# GrooveGrid.net
KiCad netlist of a schematic drawn in EAGLE
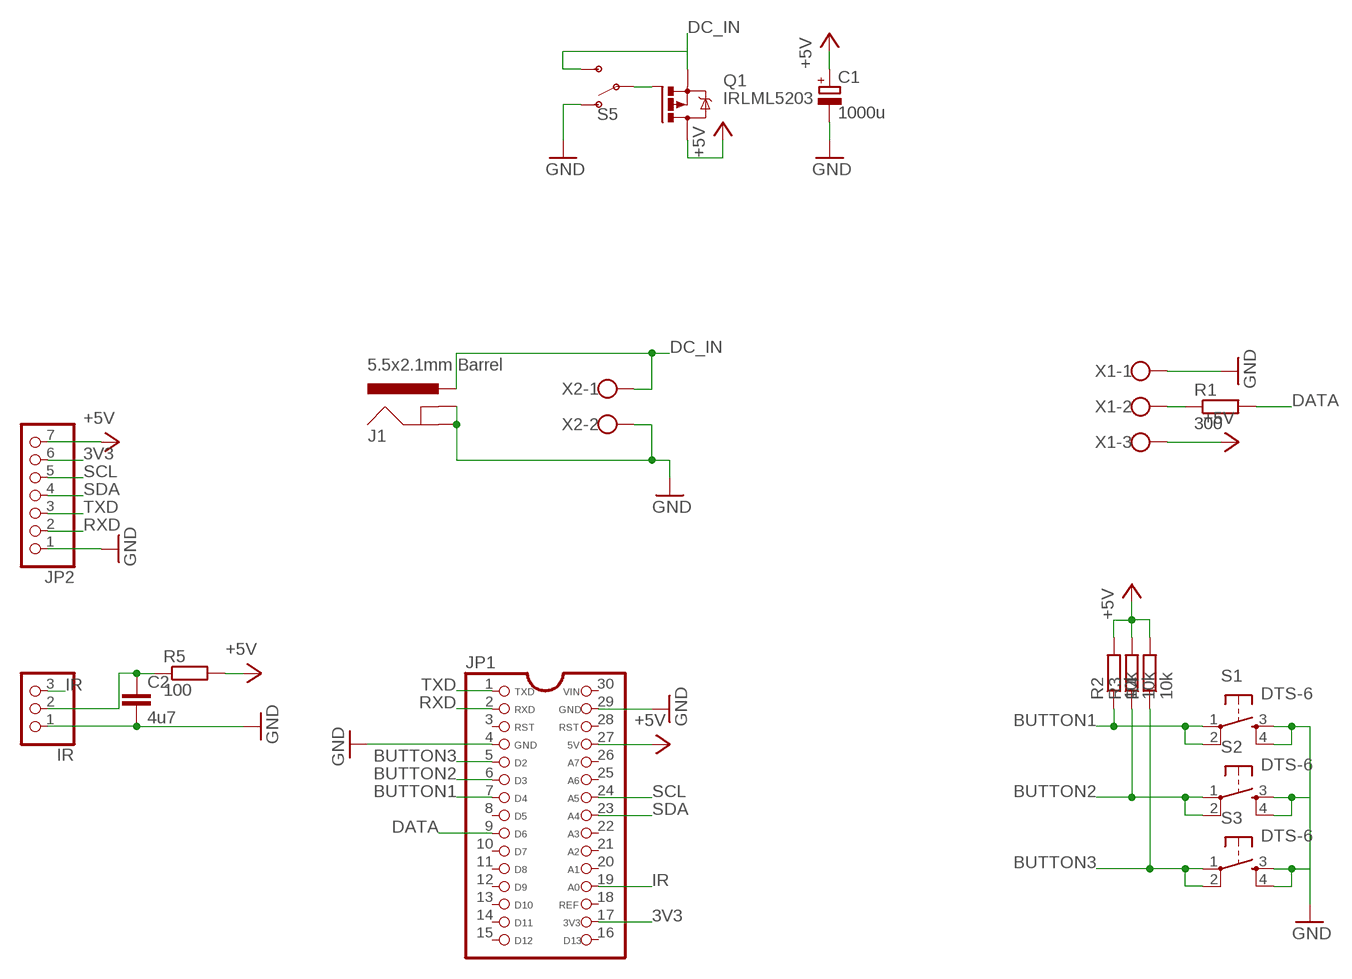
[diagram p0: schematic, sheet 1]

(export (version "E")
  (design (tool "Eeschema 10.0.6"))
  (components
    (comp (ref "C1")
      (value "1000u")
      (footprint "eagle-import:E3,5-10")
      (libsource (lib "eagle-import") (part "CPOL-EUE3.5-10"))
    )
    (comp (ref "C2")
      (value "4u7")
      (footprint "eagle-import:C0805")
      (libsource (lib "eagle-import") (part "C-EUC0805"))
    )
    (comp (ref "IR")
      (value "PINHD-1X3")
      (footprint "eagle-import:1X03")
      (libsource (lib "eagle-import") (part "PINHD-1X3"))
    )
    (comp (ref "J1")
      (value "5.5x2.1mm Barrel")
      (footprint "eagle-import:POWER_JACK_SMD")
      (libsource (lib "eagle-import") (part "POWER_JACKSMD"))
    )
    (comp (ref "JP1")
      (value "ATMEGA_NANO_MODULE")
      (footprint "eagle-import:ATMEGA_NANO_MODULE")
      (libsource (lib "eagle-import") (part "ATMEGA_NANO_MODULE"))
    )
    (comp (ref "JP2")
      (value "PINHD-1X7")
      (footprint "eagle-import:1X07")
      (libsource (lib "eagle-import") (part "PINHD-1X7"))
    )
    (comp (ref "Q1")
      (value "IRLML5203")
      (footprint "eagle-import:MICRO3")
      (libsource (lib "eagle-import") (part "IRLML5203"))
    )
    (comp (ref "R1")
      (value "300")
      (footprint "eagle-import:M0805")
      (libsource (lib "eagle-import") (part "R-EU_M0805"))
    )
    (comp (ref "R2")
      (value "10k")
      (footprint "eagle-import:M0805")
      (libsource (lib "eagle-import") (part "R-EU_M0805"))
    )
    (comp (ref "R3")
      (value "10k")
      (footprint "eagle-import:M0805")
      (libsource (lib "eagle-import") (part "R-EU_M0805"))
    )
    (comp (ref "R4")
      (value "10k")
      (footprint "eagle-import:M0805")
      (libsource (lib "eagle-import") (part "R-EU_M0805"))
    )
    (comp (ref "R5")
      (value "100")
      (footprint "eagle-import:M0805")
      (libsource (lib "eagle-import") (part "R-EU_M0805"))
    )
    (comp (ref "S1")
      (value "DTS-6")
      (footprint "eagle-import:DTS-6")
      (libsource (lib "eagle-import") (part "DTS-6"))
    )
    (comp (ref "S2")
      (value "DTS-6")
      (footprint "eagle-import:DTS-6")
      (libsource (lib "eagle-import") (part "DTS-6"))
    )
    (comp (ref "S3")
      (value "DTS-6")
      (footprint "eagle-import:DTS-6")
      (libsource (lib "eagle-import") (part "DTS-6"))
    )
    (comp (ref "S5")
      (value "SWITCH-SPDT-PTH-11.6X4.0MM")
      (footprint "eagle-import:SWITCH_SPDT_PTH_11.6X4.0MM")
      (libsource (lib "eagle-import") (part "SWITCH-SPDT-PTH-11.6X4.0MM"))
    )
    (comp (ref "X1")
      (value "W237-103")
      (footprint "eagle-import:W237-103")
      (fields (field (name "MPN") "237-103"))
      (libsource (lib "eagle-import") (part "W237-103"))
    )
    (comp (ref "X2")
      (value "W237-102")
      (footprint "eagle-import:W237-102")
      (fields (field (name "MPN") "237-102"))
      (libsource (lib "eagle-import") (part "W237-102"))
    )
  )
  (nets
    (net (code "1") (name "+5V") (class "Default")
      (node (ref "C1") (pin "+") (pinfunction "+_+") (pintype "passive"))
      (node (ref "JP1") (pin "27") (pinfunction "27_27") (pintype "passive"))
      (node (ref "JP2") (pin "7") (pinfunction "7_7") (pintype "passive"))
      (node (ref "Q1") (pin "3") (pinfunction "D_3") (pintype "passive"))
      (node (ref "R2") (pin "2") (pinfunction "2_2") (pintype "passive"))
      (node (ref "R3") (pin "2") (pinfunction "2_2") (pintype "passive"))
      (node (ref "R4") (pin "2") (pinfunction "2_2") (pintype "passive"))
      (node (ref "R5") (pin "2") (pinfunction "2_2") (pintype "passive"))
      (node (ref "X1") (pin "3") (pinfunction "KL_3") (pintype "passive"))
    )
    (net (code "2") (name "/3V3") (class "Default")
      (node (ref "JP1") (pin "17") (pinfunction "17_17") (pintype "passive"))
      (node (ref "JP2") (pin "6") (pinfunction "6_6") (pintype "passive"))
    )
    (net (code "3") (name "/BUTTON1") (class "Default")
      (node (ref "JP1") (pin "7") (pinfunction "7_7") (pintype "passive"))
      (node (ref "R2") (pin "1") (pinfunction "1_1") (pintype "passive"))
      (node (ref "S1") (pin "1") (pinfunction "1_1") (pintype "passive"))
      (node (ref "S1") (pin "2") (pinfunction "2_2") (pintype "passive"))
    )
    (net (code "4") (name "/BUTTON2") (class "Default")
      (node (ref "JP1") (pin "6") (pinfunction "6_6") (pintype "passive"))
      (node (ref "R3") (pin "1") (pinfunction "1_1") (pintype "passive"))
      (node (ref "S2") (pin "1") (pinfunction "1_1") (pintype "passive"))
      (node (ref "S2") (pin "2") (pinfunction "2_2") (pintype "passive"))
    )
    (net (code "5") (name "/BUTTON3") (class "Default")
      (node (ref "JP1") (pin "5") (pinfunction "5_5") (pintype "passive"))
      (node (ref "R4") (pin "1") (pinfunction "1_1") (pintype "passive"))
      (node (ref "S3") (pin "1") (pinfunction "1_1") (pintype "passive"))
      (node (ref "S3") (pin "2") (pinfunction "2_2") (pintype "passive"))
    )
    (net (code "6") (name "/DATA") (class "Default")
      (node (ref "JP1") (pin "9") (pinfunction "9_9") (pintype "passive"))
      (node (ref "R1") (pin "2") (pinfunction "2_2") (pintype "passive"))
    )
    (net (code "7") (name "/DC_IN") (class "Default")
      (node (ref "J1") (pin "VIN0") (pinfunction "PWR_VIN0") (pintype "bidirectional"))
      (node (ref "Q1") (pin "2") (pinfunction "S_2") (pintype "passive"))
      (node (ref "S5") (pin "3") (pinfunction "S_3") (pintype "passive"))
      (node (ref "X2") (pin "1") (pinfunction "KL_1") (pintype "passive"))
    )
    (net (code "8") (name "/IR") (class "Default")
      (node (ref "IR") (pin "3") (pinfunction "3_3") (pintype "passive"))
      (node (ref "JP1") (pin "19") (pinfunction "19_19") (pintype "passive"))
    )
    (net (code "9") (name "/RXD") (class "Default")
      (node (ref "JP1") (pin "2") (pinfunction "2_2") (pintype "passive"))
      (node (ref "JP2") (pin "2") (pinfunction "2_2") (pintype "passive"))
    )
    (net (code "10") (name "/SCL") (class "Default")
      (node (ref "JP1") (pin "24") (pinfunction "24_24") (pintype "passive"))
      (node (ref "JP2") (pin "5") (pinfunction "5_5") (pintype "passive"))
    )
    (net (code "11") (name "/SDA") (class "Default")
      (node (ref "JP1") (pin "23") (pinfunction "23_23") (pintype "passive"))
      (node (ref "JP2") (pin "4") (pinfunction "4_4") (pintype "passive"))
    )
    (net (code "12") (name "/TXD") (class "Default")
      (node (ref "JP1") (pin "1") (pinfunction "1_1") (pintype "passive"))
      (node (ref "JP2") (pin "3") (pinfunction "3_3") (pintype "passive"))
    )
    (net (code "13") (name "GND") (class "Default")
      (node (ref "C1") (pin "-") (pinfunction "-_-") (pintype "passive"))
      (node (ref "C2") (pin "2") (pinfunction "2_2") (pintype "passive"))
      (node (ref "IR") (pin "1") (pinfunction "1_1") (pintype "passive"))
      (node (ref "J1") (pin "GND") (pinfunction "GNDBREAK_GND") (pintype "bidirectional"))
      (node (ref "J1") (pin "P$4") (pinfunction "GND_P$4") (pintype "bidirectional"))
      (node (ref "JP1") (pin "29") (pinfunction "29_29") (pintype "passive"))
      (node (ref "JP1") (pin "4") (pinfunction "4_4") (pintype "passive"))
      (node (ref "JP2") (pin "1") (pinfunction "1_1") (pintype "passive"))
      (node (ref "S1") (pin "3") (pinfunction "3_3") (pintype "passive"))
      (node (ref "S1") (pin "4") (pinfunction "4_4") (pintype "passive"))
      (node (ref "S2") (pin "3") (pinfunction "3_3") (pintype "passive"))
      (node (ref "S2") (pin "4") (pinfunction "4_4") (pintype "passive"))
      (node (ref "S3") (pin "3") (pinfunction "3_3") (pintype "passive"))
      (node (ref "S3") (pin "4") (pinfunction "4_4") (pintype "passive"))
      (node (ref "S5") (pin "1") (pinfunction "O_1") (pintype "passive"))
      (node (ref "X1") (pin "1") (pinfunction "KL_1") (pintype "passive"))
      (node (ref "X2") (pin "2") (pinfunction "KL_2") (pintype "passive"))
    )
    (net (code "14") (name "Net-(C2-Pad1)") (class "Default")
      (node (ref "C2") (pin "1") (pinfunction "1_1") (pintype "passive"))
      (node (ref "IR") (pin "2") (pinfunction "2_2") (pintype "passive"))
      (node (ref "R5") (pin "1") (pinfunction "1_1") (pintype "passive"))
    )
    (net (code "15") (name "Net-(Q1-G)") (class "Default")
      (node (ref "Q1") (pin "1") (pinfunction "G_1") (pintype "passive"))
      (node (ref "S5") (pin "2") (pinfunction "P_2") (pintype "passive"))
    )
    (net (code "16") (name "Net-(X1B-KL)") (class "Default")
      (node (ref "R1") (pin "1") (pinfunction "1_1") (pintype "passive"))
      (node (ref "X1") (pin "2") (pinfunction "KL_2") (pintype "passive"))
    )
    (net (code "17") (name "unconnected-(JP1-Pad3)") (class "Default")
      (node (ref "JP1") (pin "3") (pinfunction "3_3") (pintype "passive"))
    )
    (net (code "18") (name "unconnected-(JP1-Pad8)") (class "Default")
      (node (ref "JP1") (pin "8") (pinfunction "8_8") (pintype "passive"))
    )
    (net (code "19") (name "unconnected-(JP1-Pad10)") (class "Default")
      (node (ref "JP1") (pin "10") (pinfunction "10_10") (pintype "passive"))
    )
    (net (code "20") (name "unconnected-(JP1-Pad11)") (class "Default")
      (node (ref "JP1") (pin "11") (pinfunction "11_11") (pintype "passive"))
    )
    (net (code "21") (name "unconnected-(JP1-Pad12)") (class "Default")
      (node (ref "JP1") (pin "12") (pinfunction "12_12") (pintype "passive"))
    )
    (net (code "22") (name "unconnected-(JP1-Pad13)") (class "Default")
      (node (ref "JP1") (pin "13") (pinfunction "13_13") (pintype "passive"))
    )
    (net (code "23") (name "unconnected-(JP1-Pad14)") (class "Default")
      (node (ref "JP1") (pin "14") (pinfunction "14_14") (pintype "passive"))
    )
    (net (code "24") (name "unconnected-(JP1-Pad15)") (class "Default")
      (node (ref "JP1") (pin "15") (pinfunction "15_15") (pintype "passive"))
    )
    (net (code "25") (name "unconnected-(JP1-Pad16)") (class "Default")
      (node (ref "JP1") (pin "16") (pinfunction "16_16") (pintype "passive"))
    )
    (net (code "26") (name "unconnected-(JP1-Pad18)") (class "Default")
      (node (ref "JP1") (pin "18") (pinfunction "18_18") (pintype "passive"))
    )
    (net (code "27") (name "unconnected-(JP1-Pad20)") (class "Default")
      (node (ref "JP1") (pin "20") (pinfunction "20_20") (pintype "passive"))
    )
    (net (code "28") (name "unconnected-(JP1-Pad21)") (class "Default")
      (node (ref "JP1") (pin "21") (pinfunction "21_21") (pintype "passive"))
    )
    (net (code "29") (name "unconnected-(JP1-Pad22)") (class "Default")
      (node (ref "JP1") (pin "22") (pinfunction "22_22") (pintype "passive"))
    )
    (net (code "30") (name "unconnected-(JP1-Pad25)") (class "Default")
      (node (ref "JP1") (pin "25") (pinfunction "25_25") (pintype "passive"))
    )
    (net (code "31") (name "unconnected-(JP1-Pad26)") (class "Default")
      (node (ref "JP1") (pin "26") (pinfunction "26_26") (pintype "passive"))
    )
    (net (code "32") (name "unconnected-(JP1-Pad28)") (class "Default")
      (node (ref "JP1") (pin "28") (pinfunction "28_28") (pintype "passive"))
    )
    (net (code "33") (name "unconnected-(JP1-Pad30)") (class "Default")
      (node (ref "JP1") (pin "30") (pinfunction "30_30") (pintype "passive"))
    )
  )
)
